# STM32_BLE_Board.net
KiCad netlist of a schematic drawn in Altium Designer
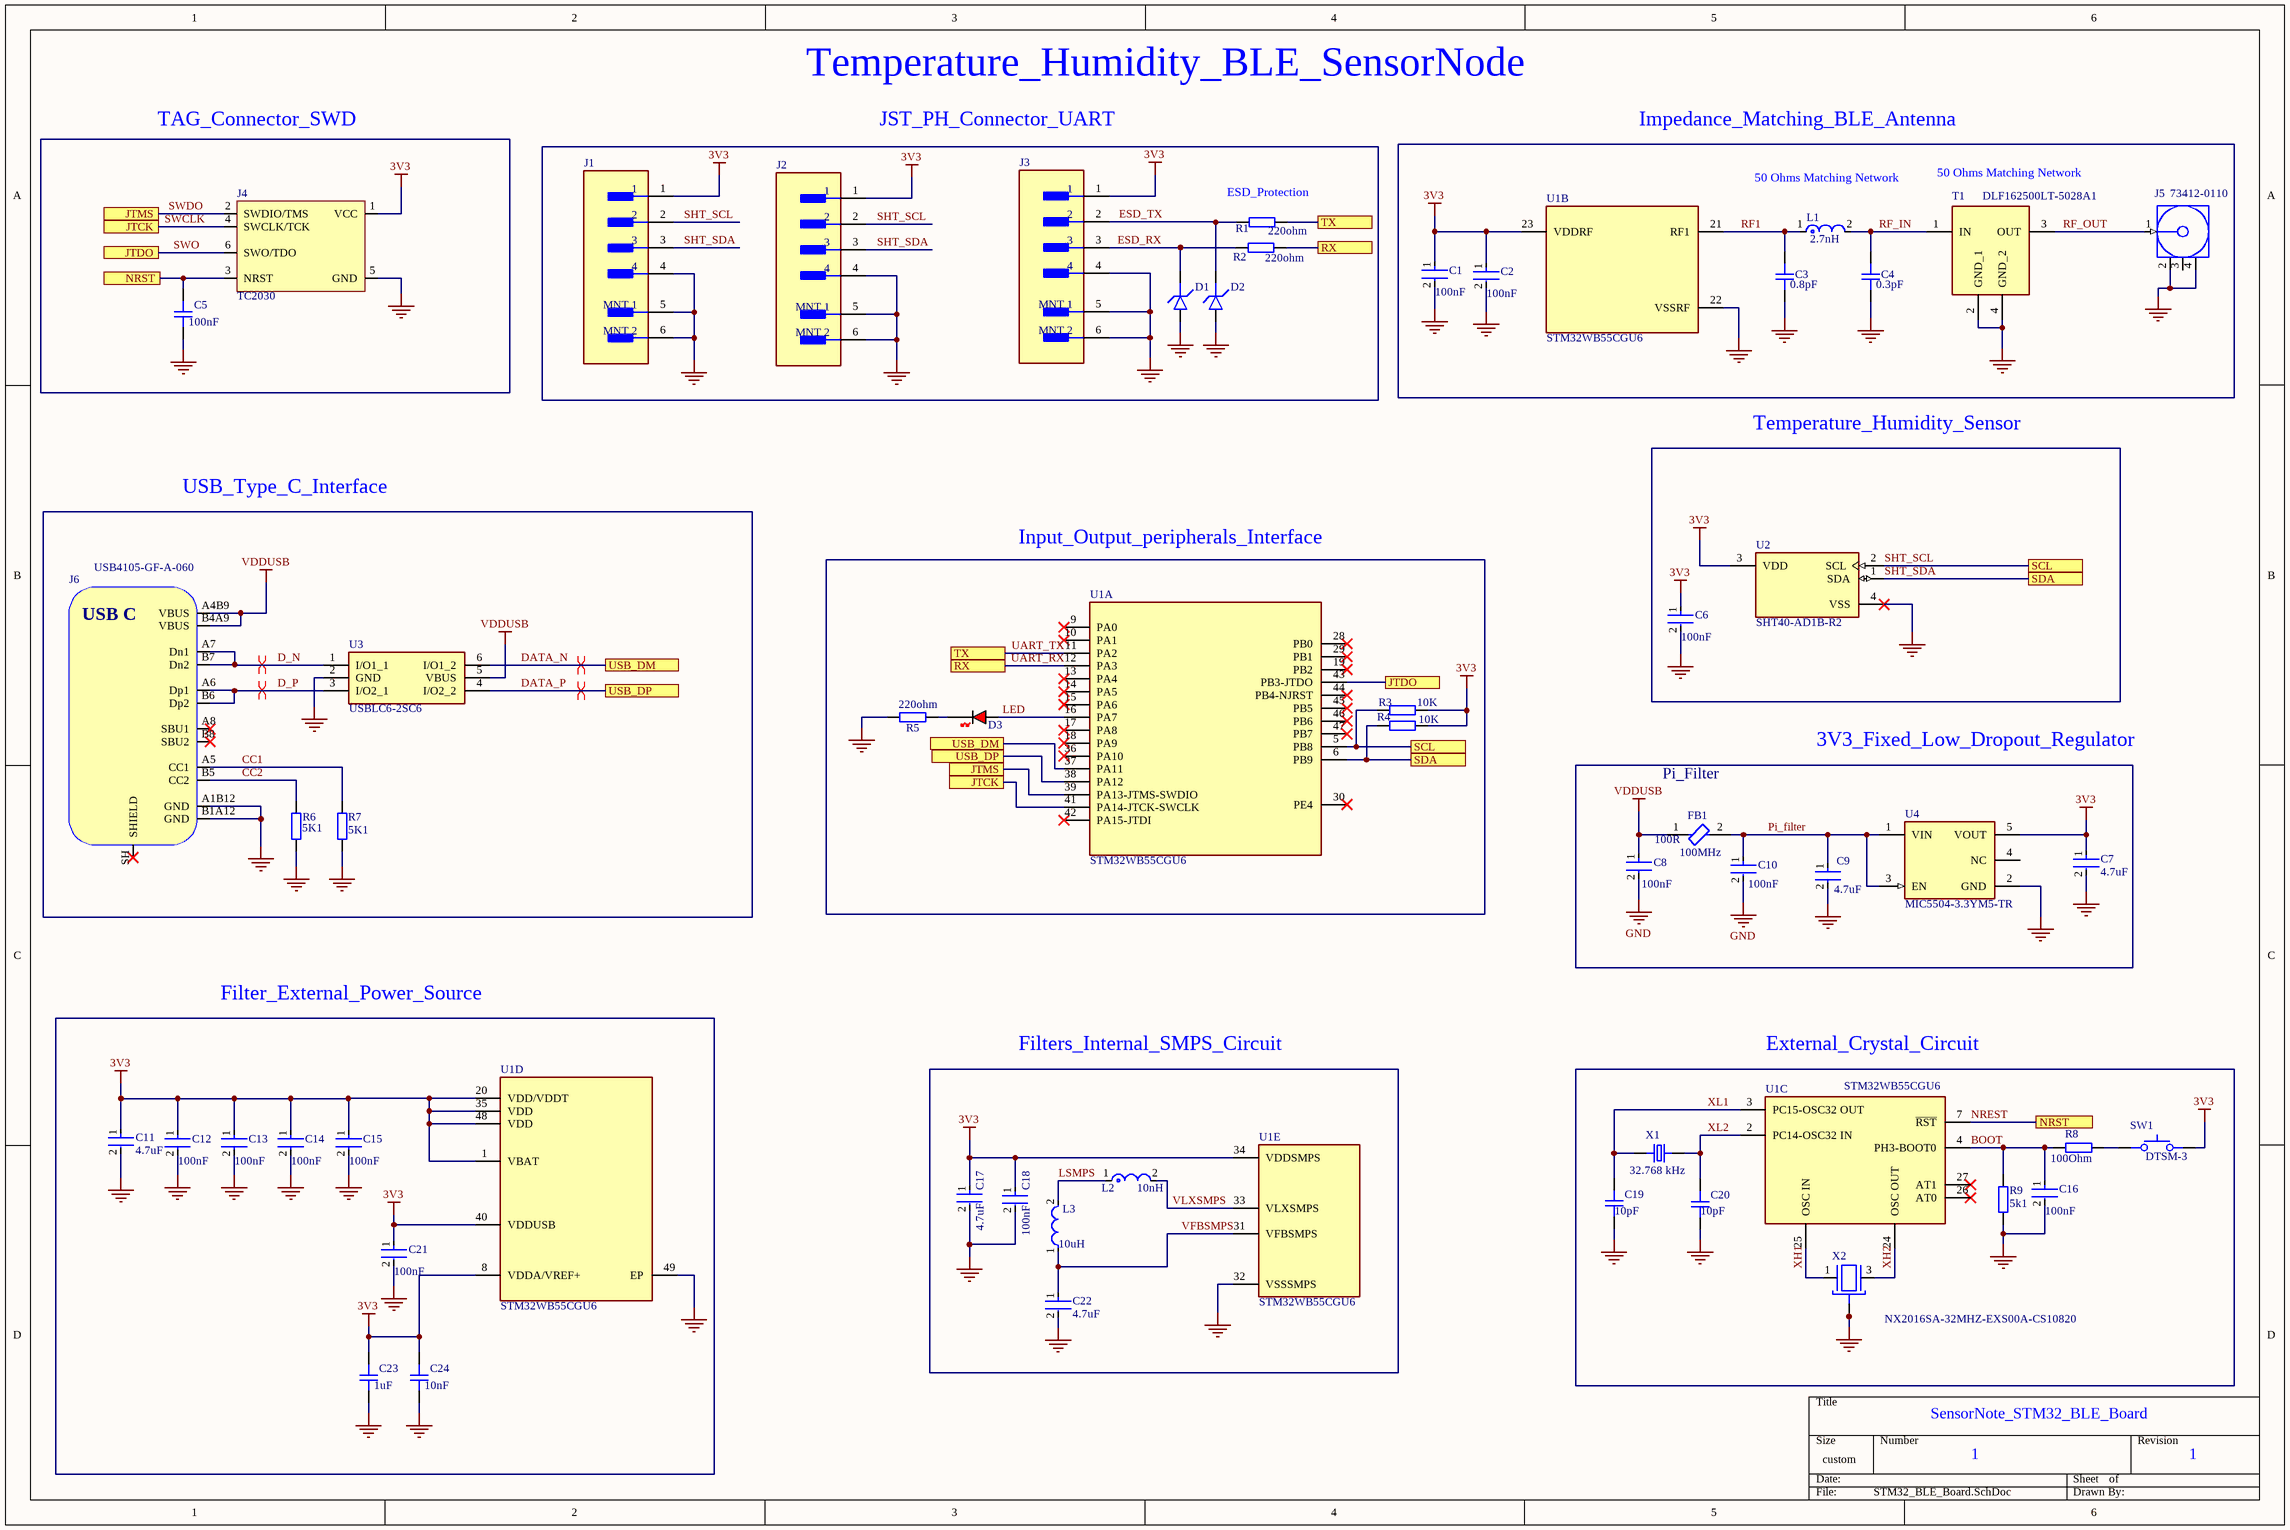
[diagram p0: STM32_BLE_Board.SchDoc]

(export (version "E")
  (design (tool "Eeschema 10.0.6"))
  (components
    (comp (ref "C1")
      (value "C0402C104K8RAC")
      (footprint "FP-C0402-BB-MFG")
      (description "C0402 0.10 μF X7R 10.00% 10 V")
      (fields
        (field (name "OCTOPART") "https://octopart.com/c0402c104k8rac-kemet-2610564")
        (field (name "MANUFACTURER") "Kemet")
        (field (name "CAPACITANCE") "100nF")
      )
      (libsource (lib "Altium Content Vault") (part "b4654b650e69147ec39a6b967a45e02"))
    )
    (comp (ref "C2")
      (value "C0402C104K8RAC")
      (footprint "FP-C0402-BB-MFG")
      (description "C0402 0.10 μF X7R 10.00% 10 V")
      (fields
        (field (name "OCTOPART") "https://octopart.com/c0402c104k8rac-kemet-2610564")
        (field (name "MANUFACTURER") "Kemet")
        (field (name "CAPACITANCE") "100nF")
      )
      (libsource (lib "Altium Content Vault") (part "b4654b650e69147ec39a6b967a45e02"))
    )
    (comp (ref "C3")
      (value "GRM1555C2AR80BA01D")
      (footprint "CAP_0402")
      (description "0.8 pF ±0.1pF 100V Ceramic Capacitor C0G, NP0 0402 (1005 Metric")
      (fields (field (name "MANUFACTURER") "Murata Electronics") (field (name "RATING") "0.8pF"))
      (libsource (lib "Schematic-Lib-PhilsLab") (part "CAP_0402"))
    )
    (comp (ref "C4")
      (value "GRM1555C1HR30WA01D")
      (footprint "CAP_0402")
      (description "Multilayer Ceramic Capacitors MLCC - SMD/SMT 0.3 pF 50 VDC 0.05 pF 0402 C0G (NP0)")
      (fields (field (name "MANUFACTURER") "Murata Electronics") (field (name "RATING") "0.3pF"))
      (libsource (lib "Schematic-Lib-PhilsLab") (part "CAP_0402"))
    )
    (comp (ref "C5")
      (value "C0402")
      (footprint "CAP_0402")
      (description "Capacitor SMD 0402")
      (fields (field (name "RATING") "100nF"))
      (libsource (lib "Schematic-Lib-PhilsLab") (part "CAP_0402"))
    )
    (comp (ref "C6")
      (value "C0402C104K8RAC")
      (footprint "FP-C0402-BB-MFG")
      (description "C0402 0.10 μF X7R 10.00% 10 V")
      (fields
        (field (name "OCTOPART") "https://octopart.com/c0402c104k8rac-kemet-2610564")
        (field (name "MANUFACTURER") "Kemet")
        (field (name "CAPACITANCE") "100nF")
      )
      (libsource (lib "Altium Content Vault") (part "b4654b650e69147ec39a6b967a45e02"))
    )
    (comp (ref "C7")
      (value "CL10A475KP8NNND")
      (footprint "FP-CL10-IPC_C")
      (description "Cap Ceramic 4.7uF 10V X5R ±10% Pad SMD 0603 +85°C T/R")
      (fields (field (name "TOLERANCE") "10%") (field (name "CAPACITANCE") "4.7uF"))
      (libsource (lib "Altium Content Vault") (part "b4654b650e69147ec39a6b967a45e02"))
    )
    (comp (ref "C8")
      (value "C0402C104K8RAC")
      (footprint "FP-C0402-BB-MFG")
      (description "C0402 0.10 μF X7R 10.00% 10 V")
      (fields
        (field (name "OCTOPART") "https://octopart.com/c0402c104k8rac-kemet-2610564")
        (field (name "MANUFACTURER") "Kemet")
        (field (name "CAPACITANCE") "100nF")
      )
      (libsource (lib "Altium Content Vault") (part "b4654b650e69147ec39a6b967a45e02"))
    )
    (comp (ref "C9")
      (value "CL10A475KP8NNND")
      (footprint "FP-CL10-IPC_C")
      (description "Cap Ceramic 4.7uF 10V X5R ±10% Pad SMD 0603 +85°C T/R")
      (fields (field (name "TOLERANCE") "10%") (field (name "CAPACITANCE") "4.7uF"))
      (libsource (lib "Altium Content Vault") (part "b4654b650e69147ec39a6b967a45e02"))
    )
    (comp (ref "C10")
      (value "C0402C104K8RAC")
      (footprint "FP-C0402-BB-MFG")
      (description "C0402 0.10 μF X7R 10.00% 10 V")
      (fields
        (field (name "OCTOPART") "https://octopart.com/c0402c104k8rac-kemet-2610564")
        (field (name "MANUFACTURER") "Kemet")
        (field (name "CAPACITANCE") "100nF")
      )
      (libsource (lib "Altium Content Vault") (part "b4654b650e69147ec39a6b967a45e02"))
    )
    (comp (ref "C11")
      (value "CL10A475KP8NNND")
      (footprint "FP-CL10-IPC_C")
      (description "Cap Ceramic 4.7uF 10V X5R ±10% Pad SMD 0603 +85°C T/R")
      (fields (field (name "TOLERANCE") "10%") (field (name "CAPACITANCE") "4.7uF"))
      (libsource (lib "Altium Content Vault") (part "b4654b650e69147ec39a6b967a45e02"))
    )
    (comp (ref "C12")
      (value "C0402C104K8RAC")
      (footprint "FP-C0402-BB-MFG")
      (description "C0402 0.10 μF X7R 10.00% 10 V")
      (fields
        (field (name "OCTOPART") "https://octopart.com/c0402c104k8rac-kemet-2610564")
        (field (name "MANUFACTURER") "Kemet")
        (field (name "CAPACITANCE") "100nF")
      )
      (libsource (lib "Altium Content Vault") (part "b4654b650e69147ec39a6b967a45e02"))
    )
    (comp (ref "C13")
      (value "C0402C104K8RAC")
      (footprint "FP-C0402-BB-MFG")
      (description "C0402 0.10 μF X7R 10.00% 10 V")
      (fields
        (field (name "OCTOPART") "https://octopart.com/c0402c104k8rac-kemet-2610564")
        (field (name "MANUFACTURER") "Kemet")
        (field (name "CAPACITANCE") "100nF")
      )
      (libsource (lib "Altium Content Vault") (part "b4654b650e69147ec39a6b967a45e02"))
    )
    (comp (ref "C14")
      (value "C0402C104K8RAC")
      (footprint "FP-C0402-BB-MFG")
      (description "C0402 0.10 μF X7R 10.00% 10 V")
      (fields
        (field (name "OCTOPART") "https://octopart.com/c0402c104k8rac-kemet-2610564")
        (field (name "MANUFACTURER") "Kemet")
        (field (name "CAPACITANCE") "100nF")
      )
      (libsource (lib "Altium Content Vault") (part "b4654b650e69147ec39a6b967a45e02"))
    )
    (comp (ref "C15")
      (value "C0402C104K8RAC")
      (footprint "FP-C0402-BB-MFG")
      (description "C0402 0.10 μF X7R 10.00% 10 V")
      (fields
        (field (name "OCTOPART") "https://octopart.com/c0402c104k8rac-kemet-2610564")
        (field (name "MANUFACTURER") "Kemet")
        (field (name "CAPACITANCE") "100nF")
      )
      (libsource (lib "Altium Content Vault") (part "b4654b650e69147ec39a6b967a45e02"))
    )
    (comp (ref "C16")
      (value "C0402C104K8RAC")
      (footprint "FP-C0402-BB-MFG")
      (description "C0402 0.10 μF X7R 10.00% 10 V")
      (fields
        (field (name "OCTOPART") "https://octopart.com/c0402c104k8rac-kemet-2610564")
        (field (name "MANUFACTURER") "Kemet")
        (field (name "CAPACITANCE") "100nF")
      )
      (libsource (lib "Altium Content Vault") (part "b4654b650e69147ec39a6b967a45e02"))
    )
    (comp (ref "C17")
      (value "CL10A475KP8NNND")
      (footprint "FP-CL10-IPC_C")
      (description "Cap Ceramic 4.7uF 10V X5R ±10% Pad SMD 0603 +85°C T/R")
      (fields (field (name "TOLERANCE") "10%") (field (name "CAPACITANCE") "4.7uF"))
      (libsource (lib "Altium Content Vault") (part "b4654b650e69147ec39a6b967a45e02"))
    )
    (comp (ref "C18")
      (value "C0402C104K8RAC")
      (footprint "FP-C0402-BB-MFG")
      (description "C0402 0.10 μF X7R 10.00% 10 V")
      (fields
        (field (name "OCTOPART") "https://octopart.com/c0402c104k8rac-kemet-2610564")
        (field (name "MANUFACTURER") "Kemet")
        (field (name "CAPACITANCE") "100nF")
      )
      (libsource (lib "Altium Content Vault") (part "b4654b650e69147ec39a6b967a45e02"))
    )
    (comp (ref "C19")
      (value "C0402")
      (footprint "CAP_0402")
      (description "Capacitor SMD 0402")
      (fields (field (name "RATING") "10pF"))
      (libsource (lib "Schematic-Lib-PhilsLab") (part "CAP_0402"))
    )
    (comp (ref "C20")
      (value "C0402")
      (footprint "CAP_0402")
      (description "Capacitor SMD 0402")
      (fields (field (name "RATING") "10pF"))
      (libsource (lib "Schematic-Lib-PhilsLab") (part "CAP_0402"))
    )
    (comp (ref "C21")
      (value "C0402C104K8RAC")
      (footprint "FP-C0402-BB-MFG")
      (description "C0402 0.10 μF X7R 10.00% 10 V")
      (fields
        (field (name "OCTOPART") "https://octopart.com/c0402c104k8rac-kemet-2610564")
        (field (name "MANUFACTURER") "Kemet")
        (field (name "CAPACITANCE") "100nF")
      )
      (libsource (lib "Altium Content Vault") (part "b4654b650e69147ec39a6b967a45e02"))
    )
    (comp (ref "C22")
      (value "CL10A475KP8NNND")
      (footprint "FP-CL10-IPC_C")
      (description "Cap Ceramic 4.7uF 10V X5R ±10% Pad SMD 0603 +85°C T/R")
      (fields (field (name "TOLERANCE") "10%") (field (name "CAPACITANCE") "4.7uF"))
      (libsource (lib "Altium Content Vault") (part "b4654b650e69147ec39a6b967a45e02"))
    )
    (comp (ref "C23")
      (value "C0402")
      (footprint "CAP_0402")
      (description "Capacitor SMD 0402")
      (fields (field (name "RATING") "1uF"))
      (libsource (lib "Schematic-Lib-PhilsLab") (part "CAP_0402"))
    )
    (comp (ref "C24")
      (value "C0402")
      (footprint "CAP_0402")
      (description "Capacitor SMD 0402")
      (fields (field (name "RATING") "10nF"))
      (libsource (lib "Schematic-Lib-PhilsLab") (part "CAP_0402"))
    )
    (comp (ref "D1")
      (value "D_TVS_0402")
      (footprint "D_0402")
      (description "Diode TVS / ESD 0402")
      (libsource (lib "Schematic-Lib-PhilsLab") (part "D_TVS_0402"))
    )
    (comp (ref "D2")
      (value "D_TVS_0402")
      (footprint "D_0402")
      (description "Diode TVS / ESD 0402")
      (libsource (lib "Schematic-Lib-PhilsLab") (part "D_TVS_0402"))
    )
    (comp (ref "D3")
      (value "RED")
      (footprint "LED_0402_RED")
      (description "LED 0402 RED SMD")
      (libsource (lib "Schematic-Lib-PhilsLab") (part "LED_0402_RED"))
    )
    (comp (ref "FB1")
      (value "BLM18EG101TN1D")
      (footprint "FP-BLM18-0_15-t0_5-MFG")
      (description "Chip Ferrite Bead, 0603, 100Ω @ 100MHz, 25%, 0.045Ω, 2A")
      (fields
        (field (name "TOLERANCE") "25%")
        (field (name "IMPEDANCE") "100R")
        (field (name "TEST FREQUENCY") "100MHz")
      )
      (libsource (lib "Altium Content Vault") (part "5f30dd21d616792df468990f7003faa"))
    )
    (comp (ref "J1")
      (value "S4B-ZR-SM4A-TF(LF)(SN)")
      (footprint "FP-S4B-ZR-SM4A-TF_LF_SN-MFG")
      (description "CONN HEADER SMD R/A 4POS 1.5MM")
      (libsource (lib "Altium Content Vault") (part "3b6f738a5616415d78381ad43816e4a"))
    )
    (comp (ref "J2")
      (value "S4B-ZR-SM4A-TF(LF)(SN)")
      (footprint "FP-S4B-ZR-SM4A-TF_LF_SN-MFG")
      (description "CONN HEADER SMD R/A 4POS 1.5MM")
      (libsource (lib "Altium Content Vault") (part "3b6f738a5616415d78381ad43816e4a"))
    )
    (comp (ref "J3")
      (value "S4B-ZR-SM4A-TF(LF)(SN)")
      (footprint "FP-S4B-ZR-SM4A-TF_LF_SN-MFG")
      (description "CONN HEADER SMD R/A 4POS 1.5MM")
      (libsource (lib "Altium Content Vault") (part "3b6f738a5616415d78381ad43816e4a"))
    )
    (comp (ref "J4")
      (value "TC2030")
      (footprint "TC2030-FP")
      (description "Tag-Connect No-Solder SWD Debug Connector DO NOT PLACE")
      (fields (field (name "MANUFACTURER") "Tag-Connect"))
      (libsource (lib "Schematic-Lib-PhilsLab") (part "TC2030"))
    )
    (comp (ref "J5")
      (value "73412-0110")
      (footprint "MOLX-73412-0110_V")
      (description "MCRF, PCB Vertical Jack Receptacle, 50 Ohm, 4-Pin SMD, RoHS, Tape and Reel")
      (libsource (lib "Altium Content Vault") (part "MOLX-73412-0110"))
    )
    (comp (ref "J6")
      (value "USB4105-GF-A-060")
      (footprint "USB4105-GF-A-060")
      (description "USB Connector Type C SMT 12 Pin")
      (fields (field (name "MANUFACTURER") "GCT"))
      (libsource (lib "Schematic-Lib-PhilsLab") (part "USB4105-GF-A-060"))
    )
    (comp (ref "L1")
      (value "LQG15HS2N7S02D")
      (footprint "FP-LQG15HH_02-IPC_C")
      (description "Multilayer type RF Inductor 2.7nH ±0.3nH 0.12Ω 800mA 0402")
      (fields (field (name "INDUCTANCE") "2.7nH"))
      (libsource (lib "Altium Content Vault") (part "4cc4b267dca4c8e51f7102f422741d8"))
    )
    (comp (ref "L2")
      (value "LQG15WZ10NJ02D")
      (footprint "FP-LQG15WH_02-MFG")
      (description "Multilayer type Inductor for Automotive 10nH ±5% 0.19Ω 500mA 0402")
      (fields (field (name "TOLERANCE") "5%") (field (name "INDUCTANCE") "10nH"))
      (libsource (lib "Altium Content Vault") (part "4cc4b267dca4c8e51f7102f422741d8"))
    )
    (comp (ref "L3")
      (value "LQM21FN100M70L")
      (footprint "FP-LQM21FN_70-MFG")
      (description "FIXED IND 10UH 100MA 780MOHM SMD")
      (fields (field (name "INDUCTANCE") "10uH") (field (name "TOLERANCE") "20%"))
      (libsource (lib "Altium Content Vault") (part "725321dda6339637d4d059423bc1c3c"))
    )
    (comp (ref "R1")
      (value "220ohm")
      (footprint "RES_0402")
      (description "Resistor SMD 0402")
      (libsource (lib "Schematic-Lib-PhilsLab") (part "RES_0402"))
    )
    (comp (ref "R2")
      (value "220ohm")
      (footprint "RES_0402")
      (description "Resistor SMD 0402")
      (libsource (lib "Schematic-Lib-PhilsLab") (part "RES_0402"))
    )
    (comp (ref "R3")
      (value "10K")
      (footprint "RES_0402")
      (description "Resistor SMD 0402")
      (libsource (lib "Schematic-Lib-PhilsLab") (part "RES_0402"))
    )
    (comp (ref "R4")
      (value "10K")
      (footprint "RES_0402")
      (description "Resistor SMD 0402")
      (libsource (lib "Schematic-Lib-PhilsLab") (part "RES_0402"))
    )
    (comp (ref "R5")
      (value "220ohm")
      (footprint "RES_0402")
      (description "Resistor SMD 0402")
      (libsource (lib "Schematic-Lib-PhilsLab") (part "RES_0402"))
    )
    (comp (ref "R6")
      (value "R0402")
      (footprint "RES_0402")
      (description "Resistor SMD 0402")
      (fields (field (name "PARAMETER 1") "5K1"))
      (libsource (lib "Schematic-Lib-PhilsLab") (part "RES_0402"))
    )
    (comp (ref "R7")
      (value "5K1")
      (footprint "RES_0402")
      (description "Resistor SMD 0402")
      (libsource (lib "Schematic-Lib-PhilsLab") (part "RES_0402"))
    )
    (comp (ref "R8")
      (value "R0402")
      (footprint "RES_0402")
      (description "Resistor SMD 0402")
      (fields (field (name "PARAMETER 1") "100Ohm"))
      (libsource (lib "Schematic-Lib-PhilsLab") (part "RES_0402"))
    )
    (comp (ref "R9")
      (value "5k1")
      (footprint "RES_0402")
      (description "Resistor SMD 0402")
      (libsource (lib "Schematic-Lib-PhilsLab") (part "RES_0402"))
    )
    (comp (ref "SW1")
      (value "DTSM-3")
      (footprint "DTSM-3")
      (description "Tactile Switch SMD SPST")
      (fields (field (name "MANUFACTURER") "Diptronics"))
      (libsource (lib "Schematic-Lib-PhilsLab") (part "DTSM-3"))
    )
    (comp (ref "T1")
      (value "DLF162500LT-5028A1")
      (footprint "DLF162500LT5028A1")
      (description "Filter")
      (fields (field (name "MOUSER PART NUMBER") "810-DLF16250LT5028A1"))
      (libsource (lib "DLF162500LT-5028A1") (part "DLF162500LT-5028A1"))
    )
    (comp (ref "U1")
      (value "STM32WB55CGU6")
      (footprint "FP-STM32WB55CGU6-IPC_B")
      (description "ULTRA-LOW-POWER DUAL CORE ARM CO")
      (fields
        (field (name "OCTOPART") "https://octopart.com/stm32wb55cgu6-stmicroelectronics-98750847")
        (field (name "MANUFACTURER") "STMicroelectronics")
      )
      (libsource (lib "") (part "CMP-12105-000013-1_2"))
    )
    (comp (ref "U2")
      (value "SHT40-AD1B-R2")
      (footprint "FP-SHT40-AD1B-R2-MFG")
      (description "SENSOR HUMIDITY 100 RH SMD")
      (libsource (lib "Altium Content Vault") (part "985d6b895d3abb4f56b1b691ea450a8"))
    )
    (comp (ref "U3")
      (value "USBLC6-2SC6")
      (footprint "SOT95P280X145-6N")
      (description "Integrated Circuit")
      (fields (field (name "MOUSER PART NUMBER") "511-USBLC6-2SC6"))
      (libsource (lib "USBLC6-2SC6") (part "USBLC6-2SC6"))
    )
    (comp (ref "U4")
      (value "MIC5504-3.3YM5-TR")
      (footprint "FP-SOT23-5LD-PL-1-MFG")
      (description "IC REG LINEAR 3.3V 300MA SOT23-5")
      (libsource (lib "Altium Content Vault") (part "96048095611b4a9579e1e315950d302"))
    )
    (comp (ref "X1")
      (value "32.768 kHz")
      (footprint "XTAL_NX2012SA-32.768K-STD-MUB-1")
      (description "32.768 kHz Â±20ppm Crystal 12.5pF 80 kOhms 2-SMD, No Lead")
      (fields (field (name "MF") "NDK America,") (field (name "MP") "NX2012SA-32.768K-STD-MUB-1"))
      (libsource (lib "NX2012SA-32.768K-STD-MUB-1") (part "NX2012SA-32.768K-STD-MUB-1"))
    )
    (comp (ref "X2")
      (value "NX2016SA-32MHZ-EXS00A-CS10820")
      (footprint "OSC_NX2016SA-24MHZ-EXS00A-CS10820")
      (description "24 MHz - Crystal 6pF 80 Ohms 4-SMD, No Lead")
      (fields
        (field (name "MP") "NX2016SA-24MHZ-EXS00A-CS10820")
        (field (name "DIGI-KEY_PART_NUMBER") "644-1365-2-ND")
      )
      (libsource (lib "NX2016SA-32MHZ-EXS00A-CS10820") (part "NX2016SA-24MHZ-EXS00A-CS10820"))
    )
  )
  (nets
    (net (code "2") (name "/BOOT") (class "Default")
      (node (ref "C16") (pin "1") (pinfunction "1_1") (pintype "passive"))
      (node (ref "R8") (pin "2") (pinfunction "2_2") (pintype "passive"))
      (node (ref "R9") (pin "2") (pinfunction "2_2") (pintype "passive"))
      (node (ref "U1") (pin "4") (pinfunction "PH3-BOOT0_4") (pintype "passive"))
    )
    (net (code "3") (name "/CC1") (class "Default")
      (node (ref "J6") (pin "A5") (pinfunction "CC1_A5") (pintype "passive"))
      (node (ref "R7") (pin "1") (pinfunction "1_1") (pintype "passive"))
    )
    (net (code "4") (name "/CC2") (class "Default")
      (node (ref "J6") (pin "B5") (pinfunction "CC2_B5") (pintype "passive"))
      (node (ref "R6") (pin "1") (pinfunction "1_1") (pintype "passive"))
    )
    (net (code "5") (name "/DATA_N") (class "Default")
      (node (ref "U1") (pin "37") (pinfunction "PA11_37") (pintype "passive"))
      (node (ref "U3") (pin "6") (pinfunction "I/O1_2_6") (pintype "passive"))
    )
    (net (code "6") (name "/DATA_P") (class "Default")
      (node (ref "U1") (pin "38") (pinfunction "PA12_38") (pintype "passive"))
      (node (ref "U3") (pin "4") (pinfunction "I/O2_2_4") (pintype "passive"))
    )
    (net (code "7") (name "/D_N") (class "Default")
      (node (ref "J6") (pin "A7") (pinfunction "Dn1_A7") (pintype "passive"))
      (node (ref "J6") (pin "B7") (pinfunction "Dn2_B7") (pintype "passive"))
      (node (ref "U3") (pin "1") (pinfunction "I/O1_1_1") (pintype "passive"))
    )
    (net (code "8") (name "/D_P") (class "Default")
      (node (ref "J6") (pin "A6") (pinfunction "Dp1_A6") (pintype "passive"))
      (node (ref "J6") (pin "B6") (pinfunction "Dp2_B6") (pintype "passive"))
      (node (ref "U3") (pin "3") (pinfunction "I/O2_1_3") (pintype "passive"))
    )
    (net (code "9") (name "/ESD_RX") (class "Default")
      (node (ref "D1") (pin "K") (pinfunction "K_K") (pintype "passive"))
      (node (ref "J3") (pin "3") (pinfunction "3_3") (pintype "passive"))
      (node (ref "R2") (pin "2") (pinfunction "2_2") (pintype "passive"))
    )
    (net (code "10") (name "/ESD_TX") (class "Default")
      (node (ref "D2") (pin "K") (pinfunction "K_K") (pintype "passive"))
      (node (ref "J3") (pin "2") (pinfunction "2_2") (pintype "passive"))
      (node (ref "R1") (pin "2") (pinfunction "2_2") (pintype "passive"))
    )
    (net (code "11") (name "/LED") (class "Default")
      (node (ref "D3") (pin "A") (pinfunction "A_A") (pintype "passive"))
      (node (ref "U1") (pin "16") (pinfunction "PA7_16") (pintype "passive"))
    )
    (net (code "12") (name "/LSMPS") (class "Default")
      (node (ref "L2") (pin "1") (pinfunction "1_1") (pintype "passive"))
      (node (ref "L3") (pin "2") (pinfunction "2_2") (pintype "passive"))
    )
    (net (code "13") (name "/NREST") (class "Default")
      (node (ref "C5") (pin "2") (pinfunction "2_2") (pintype "passive"))
      (node (ref "J4") (pin "3") (pinfunction "NRST_3") (pintype "passive"))
      (node (ref "U1") (pin "7") (pinfunction "~{RST}_7") (pintype "passive"))
    )
    (net (code "14") (name "/Pi_filter") (class "Default")
      (node (ref "C10") (pin "1") (pinfunction "1_1") (pintype "passive"))
      (node (ref "C9") (pin "1") (pinfunction "1_1") (pintype "passive"))
      (node (ref "FB1") (pin "2") (pinfunction "2_2") (pintype "passive"))
      (node (ref "U4") (pin "1") (pinfunction "VIN_1") (pintype "power_in"))
      (node (ref "U4") (pin "3") (pinfunction "EN_3") (pintype "input"))
    )
    (net (code "15") (name "/RF1") (class "Default")
      (node (ref "C3") (pin "2") (pinfunction "2_2") (pintype "passive"))
      (node (ref "L1") (pin "1") (pinfunction "1_1") (pintype "passive"))
      (node (ref "U1") (pin "21") (pinfunction "RF1_21") (pintype "passive"))
    )
    (net (code "16") (name "/RF_IN") (class "Default")
      (node (ref "C4") (pin "2") (pinfunction "2_2") (pintype "passive"))
      (node (ref "L1") (pin "2") (pinfunction "2_2") (pintype "passive"))
      (node (ref "T1") (pin "1") (pinfunction "IN_1") (pintype "passive"))
    )
    (net (code "17") (name "/RF_OUT") (class "Default")
      (node (ref "J5") (pin "1") (pinfunction "SIGNAL_1") (pintype "input"))
      (node (ref "T1") (pin "3") (pinfunction "OUT_3") (pintype "passive"))
    )
    (net (code "18") (name "/SHT_SCL") (class "Default")
      (node (ref "J1") (pin "2") (pinfunction "2_2") (pintype "passive"))
      (node (ref "J2") (pin "2") (pinfunction "2_2") (pintype "passive"))
      (node (ref "R3") (pin "1") (pinfunction "1_1") (pintype "passive"))
      (node (ref "U1") (pin "5") (pinfunction "PB8_5") (pintype "passive"))
      (node (ref "U2") (pin "2") (pinfunction "SCL_2") (pintype "input"))
    )
    (net (code "19") (name "/SHT_SDA") (class "Default")
      (node (ref "J1") (pin "3") (pinfunction "3_3") (pintype "passive"))
      (node (ref "J2") (pin "3") (pinfunction "3_3") (pintype "passive"))
      (node (ref "R4") (pin "1") (pinfunction "1_1") (pintype "passive"))
      (node (ref "U1") (pin "6") (pinfunction "PB9_6") (pintype "passive"))
      (node (ref "U2") (pin "1") (pinfunction "SDA_1") (pintype "bidirectional"))
    )
    (net (code "20") (name "/SWCLK") (class "Default")
      (node (ref "J4") (pin "4") (pinfunction "SWCLK/TCK_4") (pintype "passive"))
      (node (ref "U1") (pin "41") (pinfunction "PA14-JTCK-SWCLK_41") (pintype "passive"))
    )
    (net (code "21") (name "/SWDO") (class "Default")
      (node (ref "J4") (pin "2") (pinfunction "SWDIO/TMS_2") (pintype "passive"))
      (node (ref "U1") (pin "39") (pinfunction "PA13-JTMS-SWDIO_39") (pintype "passive"))
    )
    (net (code "22") (name "/SWO") (class "Default")
      (node (ref "J4") (pin "6") (pinfunction "SWO/TDO_6") (pintype "passive"))
      (node (ref "U1") (pin "43") (pinfunction "PB3-JTDO_43") (pintype "passive"))
    )
    (net (code "23") (name "/UART_RX") (class "Default")
      (node (ref "R2") (pin "1") (pinfunction "1_1") (pintype "passive"))
      (node (ref "U1") (pin "12") (pinfunction "PA3_12") (pintype "passive"))
    )
    (net (code "24") (name "/UART_TX") (class "Default")
      (node (ref "R1") (pin "1") (pinfunction "1_1") (pintype "passive"))
      (node (ref "U1") (pin "11") (pinfunction "PA2_11") (pintype "passive"))
    )
    (net (code "25") (name "/VFBSMPS") (class "Default")
      (node (ref "C22") (pin "1") (pinfunction "1_1") (pintype "passive"))
      (node (ref "L3") (pin "1") (pinfunction "1_1") (pintype "passive"))
      (node (ref "U1") (pin "31") (pinfunction "VFBSMPS_31") (pintype "passive"))
    )
    (net (code "26") (name "/VLXSMPS") (class "Default")
      (node (ref "L2") (pin "2") (pinfunction "2_2") (pintype "passive"))
      (node (ref "U1") (pin "33") (pinfunction "VLXSMPS_33") (pintype "passive"))
    )
    (net (code "27") (name "/XH1") (class "Default")
      (node (ref "U1") (pin "25") (pinfunction "OSC_IN_25") (pintype "passive"))
      (node (ref "X2") (pin "1") (pinfunction "1_1") (pintype "passive"))
    )
    (net (code "28") (name "/XH2") (class "Default")
      (node (ref "U1") (pin "24") (pinfunction "OSC_OUT_24") (pintype "passive"))
      (node (ref "X2") (pin "3") (pinfunction "3_3") (pintype "passive"))
    )
    (net (code "29") (name "/XL1") (class "Default")
      (node (ref "C19") (pin "2") (pinfunction "2_2") (pintype "passive"))
      (node (ref "U1") (pin "3") (pinfunction "PC15-OSC32_OUT_3") (pintype "passive"))
      (node (ref "X1") (pin "1") (pinfunction "1_1") (pintype "passive"))
    )
    (net (code "30") (name "/XL2") (class "Default")
      (node (ref "C20") (pin "2") (pinfunction "2_2") (pintype "passive"))
      (node (ref "U1") (pin "2") (pinfunction "PC14-OSC32_IN_2") (pintype "passive"))
      (node (ref "X1") (pin "2") (pinfunction "2_2") (pintype "passive"))
    )
    (net (code "31") (name "3V3") (class "Default")
      (node (ref "C1") (pin "1") (pinfunction "1_1") (pintype "passive"))
      (node (ref "C11") (pin "1") (pinfunction "1_1") (pintype "passive"))
      (node (ref "C12") (pin "1") (pinfunction "1_1") (pintype "passive"))
      (node (ref "C13") (pin "1") (pinfunction "1_1") (pintype "passive"))
      (node (ref "C14") (pin "1") (pinfunction "1_1") (pintype "passive"))
      (node (ref "C15") (pin "1") (pinfunction "1_1") (pintype "passive"))
      (node (ref "C17") (pin "1") (pinfunction "1_1") (pintype "passive"))
      (node (ref "C18") (pin "1") (pinfunction "1_1") (pintype "passive"))
      (node (ref "C2") (pin "1") (pinfunction "1_1") (pintype "passive"))
      (node (ref "C21") (pin "1") (pinfunction "1_1") (pintype "passive"))
      (node (ref "C23") (pin "2") (pinfunction "2_2") (pintype "passive"))
      (node (ref "C24") (pin "2") (pinfunction "2_2") (pintype "passive"))
      (node (ref "C6") (pin "1") (pinfunction "1_1") (pintype "passive"))
      (node (ref "C7") (pin "1") (pinfunction "1_1") (pintype "passive"))
      (node (ref "J1") (pin "1") (pinfunction "1_1") (pintype "passive"))
      (node (ref "J2") (pin "1") (pinfunction "1_1") (pintype "passive"))
      (node (ref "J3") (pin "1") (pinfunction "1_1") (pintype "passive"))
      (node (ref "J4") (pin "1") (pinfunction "VCC_1") (pintype "passive"))
      (node (ref "R3") (pin "2") (pinfunction "2_2") (pintype "passive"))
      (node (ref "R4") (pin "2") (pinfunction "2_2") (pintype "passive"))
      (node (ref "SW1") (pin "2") (pintype "passive"))
      (node (ref "U1") (pin "1") (pinfunction "VBAT_1") (pintype "passive"))
      (node (ref "U1") (pin "20") (pinfunction "VDD/VDDT_20") (pintype "passive"))
      (node (ref "U1") (pin "23") (pinfunction "VDDRF_23") (pintype "passive"))
      (node (ref "U1") (pin "34") (pinfunction "VDDSMPS_34") (pintype "passive"))
      (node (ref "U1") (pin "35") (pinfunction "VDD_35") (pintype "passive"))
      (node (ref "U1") (pin "40") (pinfunction "VDDUSB_40") (pintype "passive"))
      (node (ref "U1") (pin "48") (pinfunction "VDD_48") (pintype "passive"))
      (node (ref "U1") (pin "8") (pinfunction "VDDA/VREF+_8") (pintype "passive"))
      (node (ref "U2") (pin "3") (pinfunction "VDD_3") (pintype "power_in"))
      (node (ref "U4") (pin "5") (pinfunction "VOUT_5") (pintype "power_in"))
    )
    (net (code "32") (name "GND") (class "Default")
      (node (ref "C1") (pin "2") (pinfunction "2_2") (pintype "passive"))
      (node (ref "C10") (pin "2") (pinfunction "2_2") (pintype "passive"))
      (node (ref "C11") (pin "2") (pinfunction "2_2") (pintype "passive"))
      (node (ref "C12") (pin "2") (pinfunction "2_2") (pintype "passive"))
      (node (ref "C13") (pin "2") (pinfunction "2_2") (pintype "passive"))
      (node (ref "C14") (pin "2") (pinfunction "2_2") (pintype "passive"))
      (node (ref "C15") (pin "2") (pinfunction "2_2") (pintype "passive"))
      (node (ref "C16") (pin "2") (pinfunction "2_2") (pintype "passive"))
      (node (ref "C17") (pin "2") (pinfunction "2_2") (pintype "passive"))
      (node (ref "C18") (pin "2") (pinfunction "2_2") (pintype "passive"))
      (node (ref "C19") (pin "1") (pinfunction "1_1") (pintype "passive"))
      (node (ref "C2") (pin "2") (pinfunction "2_2") (pintype "passive"))
      (node (ref "C20") (pin "1") (pinfunction "1_1") (pintype "passive"))
      (node (ref "C21") (pin "2") (pinfunction "2_2") (pintype "passive"))
      (node (ref "C22") (pin "2") (pinfunction "2_2") (pintype "passive"))
      (node (ref "C23") (pin "1") (pinfunction "1_1") (pintype "passive"))
      (node (ref "C24") (pin "1") (pinfunction "1_1") (pintype "passive"))
      (node (ref "C3") (pin "1") (pinfunction "1_1") (pintype "passive"))
      (node (ref "C4") (pin "1") (pinfunction "1_1") (pintype "passive"))
      (node (ref "C5") (pin "1") (pinfunction "1_1") (pintype "passive"))
      (node (ref "C6") (pin "2") (pinfunction "2_2") (pintype "passive"))
      (node (ref "C7") (pin "2") (pinfunction "2_2") (pintype "passive"))
      (node (ref "C8") (pin "2") (pinfunction "2_2") (pintype "passive"))
      (node (ref "C9") (pin "2") (pinfunction "2_2") (pintype "passive"))
      (node (ref "D1") (pin "A") (pinfunction "A_A") (pintype "passive"))
      (node (ref "D2") (pin "A") (pinfunction "A_A") (pintype "passive"))
      (node (ref "J1") (pin "4") (pinfunction "4_4") (pintype "passive"))
      (node (ref "J1") (pin "5") (pinfunction "MNT_1_5") (pintype "passive"))
      (node (ref "J1") (pin "6") (pinfunction "MNT_2_6") (pintype "passive"))
      (node (ref "J2") (pin "4") (pinfunction "4_4") (pintype "passive"))
      (node (ref "J2") (pin "5") (pinfunction "MNT_1_5") (pintype "passive"))
      (node (ref "J2") (pin "6") (pinfunction "MNT_2_6") (pintype "passive"))
      (node (ref "J3") (pin "4") (pinfunction "4_4") (pintype "passive"))
      (node (ref "J3") (pin "5") (pinfunction "MNT_1_5") (pintype "passive"))
      (node (ref "J3") (pin "6") (pinfunction "MNT_2_6") (pintype "passive"))
      (node (ref "J4") (pin "5") (pinfunction "GND_5") (pintype "passive"))
      (node (ref "J5") (pin "2") (pinfunction "GND_2") (pintype "power_in"))
      (node (ref "J5") (pin "4") (pinfunction "GND_4") (pintype "power_in"))
      (node (ref "J6") (pin "A1B12") (pinfunction "GND_A1B12") (pintype "passive"))
      (node (ref "J6") (pin "B1A12") (pinfunction "GND_B1A12") (pintype "passive"))
      (node (ref "R5") (pin "2") (pinfunction "2_2") (pintype "passive"))
      (node (ref "R6") (pin "2") (pinfunction "2_2") (pintype "passive"))
      (node (ref "R7") (pin "2") (pinfunction "2_2") (pintype "passive"))
      (node (ref "R9") (pin "1") (pinfunction "1_1") (pintype "passive"))
      (node (ref "T1") (pin "2") (pinfunction "GND_1_2") (pintype "passive"))
      (node (ref "T1") (pin "4") (pinfunction "GND_2_4") (pintype "passive"))
      (node (ref "U1") (pin "22") (pinfunction "VSSRF_22") (pintype "passive"))
      (node (ref "U1") (pin "32") (pinfunction "VSSSMPS_32") (pintype "passive"))
      (node (ref "U1") (pin "49") (pinfunction "EP_49") (pintype "open_collector"))
      (node (ref "U2") (pin "4") (pinfunction "VSS_4") (pintype "power_in"))
      (node (ref "U3") (pin "2") (pinfunction "GND_2") (pintype "passive"))
      (node (ref "U4") (pin "2") (pinfunction "GND_2") (pintype "power_in"))
      (node (ref "X2") (pin "2") (pinfunction "GND_2") (pintype "power_in"))
      (node (ref "X2") (pin "4") (pinfunction "GND_4") (pintype "power_in"))
    )
    (net (code "33") (name "Net-(D3-PadK)") (class "Default")
      (node (ref "D3") (pin "K") (pinfunction "K_K") (pintype "passive"))
      (node (ref "R5") (pin "1") (pinfunction "1_1") (pintype "passive"))
    )
    (net (code "34") (name "Net-(R8-Pad1)") (class "Default")
      (node (ref "R8") (pin "1") (pinfunction "1_1") (pintype "passive"))
      (node (ref "SW1") (pin "1") (pintype "passive"))
    )
    (net (code "35") (name "VDDUSB") (class "Default")
      (node (ref "C8") (pin "1") (pinfunction "1_1") (pintype "passive"))
      (node (ref "FB1") (pin "1") (pinfunction "1_1") (pintype "passive"))
      (node (ref "J6") (pin "A4B9") (pinfunction "VBUS_A4B9") (pintype "passive"))
      (node (ref "J6") (pin "B4A9") (pinfunction "VBUS_B4A9") (pintype "passive"))
      (node (ref "U3") (pin "5") (pinfunction "VBUS_5") (pintype "passive"))
    )
    (net (code "36") (name "unconnected-(J5-GND-Pad3)") (class "Default")
      (node (ref "J5") (pin "3") (pinfunction "GND_3") (pintype "power_in"))
    )
    (net (code "37") (name "unconnected-(J6-SBU1-PadA8)") (class "Default")
      (node (ref "J6") (pin "A8") (pinfunction "SBU1_A8") (pintype "passive+no_connect"))
    )
    (net (code "38") (name "unconnected-(J6-SBU2-PadB8)") (class "Default")
      (node (ref "J6") (pin "B8") (pinfunction "SBU2_B8") (pintype "passive+no_connect"))
    )
    (net (code "39") (name "unconnected-(J6-SHIELD-PadSH)") (class "Default")
      (node (ref "J6") (pin "SH") (pinfunction "SHIELD_SH") (pintype "passive+no_connect"))
    )
    (net (code "40") (name "unconnected-(U1A-PA0-Pad9)") (class "Default")
      (node (ref "U1") (pin "9") (pinfunction "PA0_9") (pintype "passive+no_connect"))
    )
    (net (code "41") (name "unconnected-(U1A-PA1-Pad10)") (class "Default")
      (node (ref "U1") (pin "10") (pinfunction "PA1_10") (pintype "passive+no_connect"))
    )
    (net (code "42") (name "unconnected-(U1A-PA4-Pad13)") (class "Default")
      (node (ref "U1") (pin "13") (pinfunction "PA4_13") (pintype "passive+no_connect"))
    )
    (net (code "43") (name "unconnected-(U1A-PA5-Pad14)") (class "Default")
      (node (ref "U1") (pin "14") (pinfunction "PA5_14") (pintype "passive+no_connect"))
    )
    (net (code "44") (name "unconnected-(U1A-PA6-Pad15)") (class "Default")
      (node (ref "U1") (pin "15") (pinfunction "PA6_15") (pintype "passive+no_connect"))
    )
    (net (code "45") (name "unconnected-(U1A-PA8-Pad17)") (class "Default")
      (node (ref "U1") (pin "17") (pinfunction "PA8_17") (pintype "passive+no_connect"))
    )
    (net (code "46") (name "unconnected-(U1A-PA9-Pad18)") (class "Default")
      (node (ref "U1") (pin "18") (pinfunction "PA9_18") (pintype "passive+no_connect"))
    )
    (net (code "47") (name "unconnected-(U1A-PA10-Pad36)") (class "Default")
      (node (ref "U1") (pin "36") (pinfunction "PA10_36") (pintype "passive+no_connect"))
    )
    (net (code "48") (name "unconnected-(U1A-PA15-JTDI-Pad42)") (class "Default")
      (node (ref "U1") (pin "42") (pinfunction "PA15-JTDI_42") (pintype "passive+no_connect"))
    )
    (net (code "49") (name "unconnected-(U1A-PB0-Pad28)") (class "Default")
      (node (ref "U1") (pin "28") (pinfunction "PB0_28") (pintype "passive+no_connect"))
    )
    (net (code "50") (name "unconnected-(U1A-PB1-Pad29)") (class "Default")
      (node (ref "U1") (pin "29") (pinfunction "PB1_29") (pintype "passive+no_connect"))
    )
    (net (code "51") (name "unconnected-(U1A-PB2-Pad19)") (class "Default")
      (node (ref "U1") (pin "19") (pinfunction "PB2_19") (pintype "passive+no_connect"))
    )
    (net (code "52") (name "unconnected-(U1A-PB4-NJRST-Pad44)") (class "Default")
      (node (ref "U1") (pin "44") (pinfunction "PB4-NJRST_44") (pintype "passive+no_connect"))
    )
    (net (code "53") (name "unconnected-(U1A-PB5-Pad45)") (class "Default")
      (node (ref "U1") (pin "45") (pinfunction "PB5_45") (pintype "passive+no_connect"))
    )
    (net (code "54") (name "unconnected-(U1A-PB6-Pad46)") (class "Default")
      (node (ref "U1") (pin "46") (pinfunction "PB6_46") (pintype "passive+no_connect"))
    )
    (net (code "55") (name "unconnected-(U1A-PB7-Pad47)") (class "Default")
      (node (ref "U1") (pin "47") (pinfunction "PB7_47") (pintype "passive+no_connect"))
    )
    (net (code "56") (name "unconnected-(U1A-PE4-Pad30)") (class "Default")
      (node (ref "U1") (pin "30") (pinfunction "PE4_30") (pintype "passive+no_connect"))
    )
    (net (code "57") (name "unconnected-(U1C-AT0-Pad26)") (class "Default")
      (node (ref "U1") (pin "26") (pinfunction "AT0_26") (pintype "passive+no_connect"))
    )
    (net (code "58") (name "unconnected-(U1C-AT1-Pad27)") (class "Default")
      (node (ref "U1") (pin "27") (pinfunction "AT1_27") (pintype "passive+no_connect"))
    )
    (net (code "59") (name "unconnected-(U4-NC-Pad4)") (class "Default")
      (node (ref "U4") (pin "4") (pinfunction "NC_4") (pintype "passive"))
    )
  )
)
